# STM32F103C8T6.net
KiCad netlist of a schematic drawn in Altium Designer
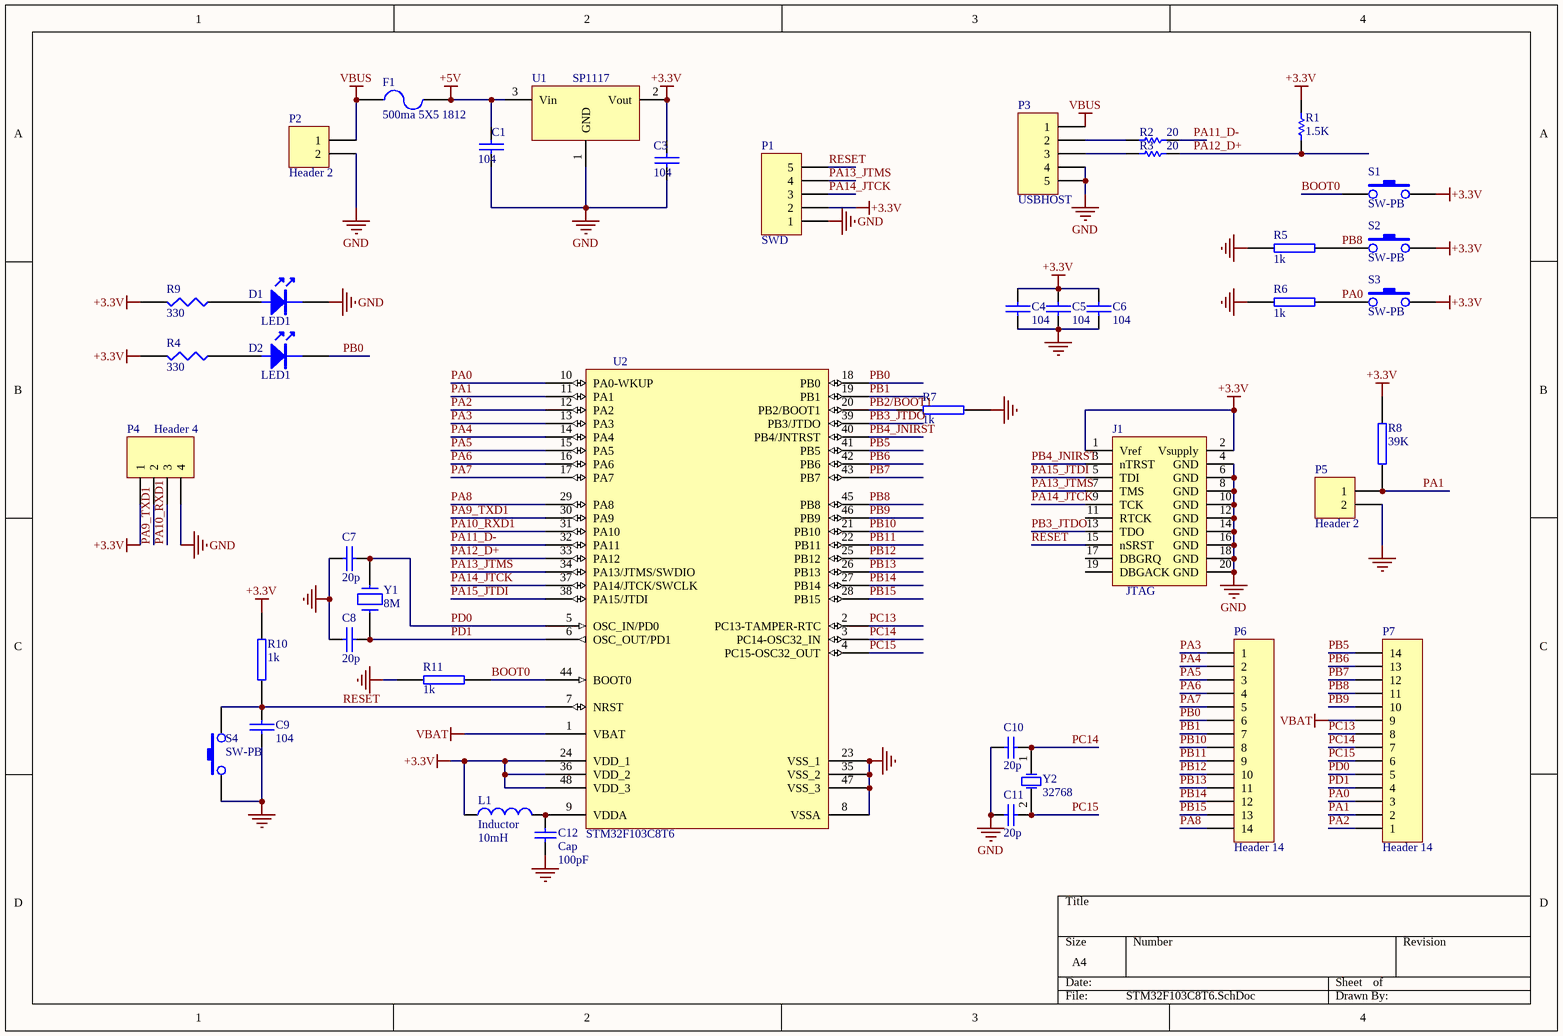
[diagram p0: STM32F103C8T6.SchDoc]

(export (version "E")
  (design (tool "Eeschema 10.0.6"))
  (components
    (comp (ref "C1")
      (value "104")
      (footprint "0805C1")
      (description "Capacitor")
      (libsource (lib "*") (part "CAP"))
    )
    (comp (ref "C3")
      (value "104")
      (footprint "0805C1")
      (description "Capacitor")
      (libsource (lib "*") (part "CAP"))
    )
    (comp (ref "C4")
      (value "104")
      (footprint "0805C1")
      (description "Capacitor")
      (libsource (lib "*") (part "CAP"))
    )
    (comp (ref "C5")
      (value "104")
      (footprint "0805C1")
      (description "Capacitor")
      (libsource (lib "*") (part "CAP"))
    )
    (comp (ref "C6")
      (value "104")
      (footprint "0805C1")
      (description "Capacitor")
      (libsource (lib "*") (part "CAP"))
    )
    (comp (ref "C7")
      (value "20p")
      (footprint "0805C1")
      (description "Capacitor")
      (libsource (lib "*") (part "CAP"))
    )
    (comp (ref "C8")
      (value "20p")
      (footprint "0805C1")
      (description "Capacitor")
      (libsource (lib "*") (part "CAP"))
    )
    (comp (ref "C9")
      (value "104")
      (footprint "0805C1")
      (description "Capacitor")
      (libsource (lib "*") (part "CAP"))
    )
    (comp (ref "C10")
      (value "20p")
      (footprint "0805C1")
      (description "Capacitor")
      (fields (field (name "Comment") "Cap") (field (name "PUBLISHER") "Altium Limited"))
      (libsource (lib "Miscellaneous Devices") (part "Cap"))
    )
    (comp (ref "C11")
      (value "20p")
      (footprint "0805C1")
      (description "Capacitor")
      (fields (field (name "Comment") "Cap") (field (name "PUBLISHER") "Altium Limited"))
      (libsource (lib "Miscellaneous Devices") (part "Cap"))
    )
    (comp (ref "C12")
      (value "Cap")
      (footprint "0805C1")
      (description "Capacitor")
      (fields (field (name "ALTIUM_VALUE") "100pF") (field (name "PUBLISHER") "Altium Limited"))
      (libsource (lib "Miscellaneous Devices") (part "Cap"))
    )
    (comp (ref "D1") (value "LED1") (footprint "0805LED") (libsource (lib "*") (part "LED")))
    (comp (ref "D2") (value "LED1") (footprint "0805LED") (libsource (lib "*") (part "LED")))
    (comp (ref "F1")
      (value "500ma 5X5 1812")
      (footprint "1812R")
      (description "Fuse")
      (fields (field (name "PUBLISHER") "Altium Limited"))
      (libsource (lib "Miscellaneous Devices") (part "Fuse 2"))
    )
    (comp (ref "J1") (value "JTAG") (footprint "HDR2X10") (libsource (lib "hhic") (part "JTAG")))
    (comp (ref "L1")
      (value "Inductor")
      (footprint "0805R1")
      (fields (field (name "ALTIUM_VALUE") "10mH") (field (name "PUBLISHER") "Altium Limited"))
      (libsource (lib "Miscellaneous Devices") (part "Inductor"))
    )
    (comp (ref "P1")
      (value "SWD")
      (footprint "HDR1X5")
      (description "Header, 5-Pin")
      (fields (field (name "PUBLISHER") "Altium Limited"))
      (libsource (lib "") (part "Header 5_1"))
    )
    (comp (ref "P2")
      (value "Header 2")
      (footprint "5VINPUT")
      (description "Header, 2-Pin")
      (fields (field (name "PUBLISHER") "Altium Limited"))
      (libsource (lib "Miscellaneous Connectors") (part "Header 2"))
    )
    (comp (ref "P3")
      (value "USBHOST")
      (footprint "USB_mini")
      (description "Header, 5-Pin")
      (fields (field (name "PUBLISHER") "Altium Limited"))
      (libsource (lib "Miscellaneous Connectors") (part "Header 5"))
    )
    (comp (ref "P4")
      (value "Header 4")
      (footprint "HDR1X4")
      (description "Header, 4-Pin")
      (fields (field (name "PUBLISHER") "Altium Limited"))
      (libsource (lib "Miscellaneous Connectors") (part "Header 4"))
    )
    (comp (ref "P5")
      (value "Header 2")
      (footprint "HDR1X2")
      (description "Header, 2-Pin")
      (fields (field (name "PUBLISHER") "Altium Limited"))
      (libsource (lib "Miscellaneous Connectors") (part "Header 2"))
    )
    (comp (ref "P6")
      (value "Header 14")
      (footprint "HDR1X14")
      (description "Header, 14-Pin")
      (fields (field (name "PUBLISHER") "Altium Limited"))
      (libsource (lib "Miscellaneous Connectors") (part "Header 14"))
    )
    (comp (ref "P7")
      (value "Header 14")
      (footprint "HDR1X14")
      (description "Header, 14-Pin")
      (fields (field (name "PUBLISHER") "Altium Limited"))
      (libsource (lib "") (part "Header 14_1"))
    )
    (comp (ref "R1")
      (value "1.5K")
      (footprint "0805R1")
      (description "Semiconductor Resistor")
      (fields (field (name "Comment") "Res Semi") (field (name "PUBLISHER") "Altium Limited"))
      (libsource (lib "Miscellaneous Devices") (part "Res Semi"))
    )
    (comp (ref "R2")
      (value "20")
      (footprint "0805R1")
      (description "Semiconductor Resistor")
      (fields (field (name "Comment") "Res Semi") (field (name "PUBLISHER") "Altium Limited"))
      (libsource (lib "Miscellaneous Devices") (part "Res Semi"))
    )
    (comp (ref "R3")
      (value "20")
      (footprint "0805R1")
      (description "Semiconductor Resistor")
      (fields (field (name "Comment") "Res Semi") (field (name "PUBLISHER") "Altium Limited"))
      (libsource (lib "Miscellaneous Devices") (part "Res Semi"))
    )
    (comp (ref "R4") (value "330") (footprint "0805R1") (libsource (lib "*") (part "RES1")))
    (comp (ref "R5") (value "1k") (footprint "0805R1") (libsource (lib "*") (part "RES2")))
    (comp (ref "R6") (value "1k") (footprint "0805R1") (libsource (lib "*") (part "RES2")))
    (comp (ref "R7") (value "1k") (footprint "0805R1") (libsource (lib "*") (part "RES2")))
    (comp (ref "R8") (value "39K") (footprint "0805R1") (libsource (lib "*") (part "RES2")))
    (comp (ref "R9") (value "330") (footprint "0805R1") (libsource (lib "*") (part "RES1")))
    (comp (ref "R10") (value "1k") (footprint "0805R1") (libsource (lib "*") (part "RES2")))
    (comp (ref "R11") (value "1k") (footprint "0805R1") (libsource (lib "*") (part "RES2")))
    (comp (ref "S1") (value "SW-PB") (footprint "KEY_5*5*X") (libsource (lib "*") (part "SW-PB")))
    (comp (ref "S2") (value "SW-PB") (footprint "KEY_5*5*X") (libsource (lib "*") (part "SW-PB")))
    (comp (ref "S3") (value "SW-PB") (footprint "KEY_5*5*X") (libsource (lib "*") (part "SW-PB")))
    (comp (ref "S4") (value "SW-PB") (footprint "KEY_5*5*X") (libsource (lib "*") (part "SW-PB")))
    (comp (ref "U1") (value "SP1117") (footprint "SOT-223") (libsource (lib "hhregulator") (part "SP1117")))
    (comp (ref "U2")
      (value "STM32F103C8T6")
      (footprint "LQFP48_M")
      (description "STM32 ARM-based 32-bit MCU with 64 Kbytes Flash, 48-pin LQFP, Industrial Temperature")
      (fields (field (name "PUBLISHER") "*"))
      (libsource (lib "*") (part "STM32F103C8T6"))
    )
    (comp (ref "Y1")
      (value "8M")
      (footprint "XTAL_smd1")
      (description "Crystal")
      (libsource (lib "*") (part "CRYSTAL"))
    )
    (comp (ref "Y2")
      (value "32768")
      (footprint "XTAL_32768_HH")
      (description "Crystal Oscillator")
      (fields (field (name "PUBLISHER") "Altium Limited"))
      (libsource (lib "Miscellaneous Devices") (part "XTAL"))
    )
  )
  (nets
    (net (code "1") (name "+3.3V") (class "Default")
      (node (ref "C3") (pin "1") (pinfunction "1_1") (pintype "passive"))
      (node (ref "C4") (pin "2") (pinfunction "2_2") (pintype "passive"))
      (node (ref "C5") (pin "2") (pinfunction "2_2") (pintype "passive"))
      (node (ref "C6") (pin "2") (pinfunction "2_2") (pintype "passive"))
      (node (ref "J1") (pin "1") (pinfunction "Vref_1") (pintype "passive"))
      (node (ref "J1") (pin "2") (pinfunction "Vsupply_2") (pintype "passive"))
      (node (ref "L1") (pin "1") (pinfunction "1_1") (pintype "passive"))
      (node (ref "P1") (pin "2") (pinfunction "2_2") (pintype "passive"))
      (node (ref "P4") (pin "1") (pinfunction "1_1") (pintype "passive"))
      (node (ref "R1") (pin "1") (pinfunction "1_1") (pintype "passive"))
      (node (ref "R10") (pin "2") (pinfunction "2_2") (pintype "passive"))
      (node (ref "R4") (pin "2") (pinfunction "2_2") (pintype "passive"))
      (node (ref "R8") (pin "1") (pinfunction "1_1") (pintype "passive"))
      (node (ref "R9") (pin "2") (pinfunction "2_2") (pintype "passive"))
      (node (ref "S1") (pin "2") (pinfunction "2_2") (pintype "passive"))
      (node (ref "S2") (pin "1") (pinfunction "1_1") (pintype "passive"))
      (node (ref "S3") (pin "1") (pinfunction "1_1") (pintype "passive"))
      (node (ref "U1") (pin "2") (pinfunction "Vout_2") (pintype "passive"))
      (node (ref "U2") (pin "24") (pinfunction "VDD_1_24") (pintype "power_in"))
      (node (ref "U2") (pin "36") (pinfunction "VDD_2_36") (pintype "power_in"))
      (node (ref "U2") (pin "48") (pinfunction "VDD_3_48") (pintype "power_in"))
    )
    (net (code "2") (name "+5V") (class "Default")
      (node (ref "C1") (pin "1") (pinfunction "1_1") (pintype "passive"))
      (node (ref "F1") (pin "2") (pinfunction "2_2") (pintype "passive"))
      (node (ref "U1") (pin "3") (pinfunction "Vin_3") (pintype "passive"))
    )
    (net (code "3") (name "/BOOT0") (class "Default")
      (node (ref "R11") (pin "1") (pinfunction "1_1") (pintype "passive"))
      (node (ref "S1") (pin "1") (pinfunction "1_1") (pintype "passive"))
      (node (ref "U2") (pin "44") (pinfunction "BOOT0_44") (pintype "input"))
    )
    (net (code "4") (name "/PA0") (class "Default")
      (node (ref "P7") (pin "3") (pinfunction "3_3") (pintype "passive"))
      (node (ref "R6") (pin "1") (pinfunction "1_1") (pintype "passive"))
      (node (ref "S3") (pin "2") (pinfunction "2_2") (pintype "passive"))
      (node (ref "U2") (pin "10") (pinfunction "PA0-WKUP_10") (pintype "bidirectional"))
    )
    (net (code "5") (name "/PA1") (class "Default")
      (node (ref "P5") (pin "1") (pinfunction "1_1") (pintype "passive"))
      (node (ref "P7") (pin "2") (pinfunction "2_2") (pintype "passive"))
      (node (ref "R8") (pin "2") (pinfunction "2_2") (pintype "passive"))
      (node (ref "U2") (pin "11") (pinfunction "PA1_11") (pintype "bidirectional"))
    )
    (net (code "6") (name "/PA2") (class "Default")
      (node (ref "P7") (pin "1") (pinfunction "1_1") (pintype "passive"))
      (node (ref "U2") (pin "12") (pinfunction "PA2_12") (pintype "bidirectional"))
    )
    (net (code "7") (name "/PA3") (class "Default")
      (node (ref "P6") (pin "1") (pinfunction "1_1") (pintype "passive"))
      (node (ref "U2") (pin "13") (pinfunction "PA3_13") (pintype "bidirectional"))
    )
    (net (code "8") (name "/PA4") (class "Default")
      (node (ref "P6") (pin "2") (pinfunction "2_2") (pintype "passive"))
      (node (ref "U2") (pin "14") (pinfunction "PA4_14") (pintype "bidirectional"))
    )
    (net (code "9") (name "/PA5") (class "Default")
      (node (ref "P6") (pin "3") (pinfunction "3_3") (pintype "passive"))
      (node (ref "U2") (pin "15") (pinfunction "PA5_15") (pintype "bidirectional"))
    )
    (net (code "10") (name "/PA6") (class "Default")
      (node (ref "P6") (pin "4") (pinfunction "4_4") (pintype "passive"))
      (node (ref "U2") (pin "16") (pinfunction "PA6_16") (pintype "bidirectional"))
    )
    (net (code "11") (name "/PA7") (class "Default")
      (node (ref "P6") (pin "5") (pinfunction "5_5") (pintype "passive"))
      (node (ref "U2") (pin "17") (pinfunction "PA7_17") (pintype "bidirectional"))
    )
    (net (code "12") (name "/PA8") (class "Default")
      (node (ref "P6") (pin "14") (pinfunction "14_14") (pintype "passive"))
      (node (ref "U2") (pin "29") (pinfunction "PA8_29") (pintype "bidirectional"))
    )
    (net (code "13") (name "/PA9_TXD1") (class "Default")
      (node (ref "P4") (pin "2") (pinfunction "2_2") (pintype "passive"))
      (node (ref "U2") (pin "30") (pinfunction "PA9_30") (pintype "bidirectional"))
    )
    (net (code "14") (name "/PA10_RXD1") (class "Default")
      (node (ref "P4") (pin "3") (pinfunction "3_3") (pintype "passive"))
      (node (ref "U2") (pin "31") (pinfunction "PA10_31") (pintype "bidirectional"))
    )
    (net (code "15") (name "/PA11_D-") (class "Default")
      (node (ref "R2") (pin "2") (pinfunction "2_2") (pintype "passive"))
      (node (ref "U2") (pin "32") (pinfunction "PA11_32") (pintype "bidirectional"))
    )
    (net (code "16") (name "/PA12_D+") (class "Default")
      (node (ref "R1") (pin "2") (pinfunction "2_2") (pintype "passive"))
      (node (ref "R3") (pin "2") (pinfunction "2_2") (pintype "passive"))
      (node (ref "U2") (pin "33") (pinfunction "PA12_33") (pintype "bidirectional"))
    )
    (net (code "17") (name "/PA13_JTMS") (class "Default")
      (node (ref "J1") (pin "7") (pinfunction "TMS_7") (pintype "passive"))
      (node (ref "P1") (pin "4") (pinfunction "4_4") (pintype "passive"))
      (node (ref "U2") (pin "34") (pinfunction "PA13/JTMS/SWDIO_34") (pintype "bidirectional"))
    )
    (net (code "18") (name "/PA14_JTCK") (class "Default")
      (node (ref "J1") (pin "9") (pinfunction "TCK_9") (pintype "passive"))
      (node (ref "P1") (pin "3") (pinfunction "3_3") (pintype "passive"))
      (node (ref "U2") (pin "37") (pinfunction "PA14/JTCK/SWCLK_37") (pintype "bidirectional"))
    )
    (net (code "19") (name "/PA15_JTDI") (class "Default")
      (node (ref "J1") (pin "5") (pinfunction "TDI_5") (pintype "passive"))
      (node (ref "U2") (pin "38") (pinfunction "PA15/JTDI_38") (pintype "bidirectional"))
    )
    (net (code "20") (name "/PB0") (class "Default")
      (node (ref "D2") (pin "2") (pinfunction "2_2") (pintype "passive"))
      (node (ref "P6") (pin "6") (pinfunction "6_6") (pintype "passive"))
      (node (ref "U2") (pin "18") (pinfunction "PB0_18") (pintype "bidirectional"))
    )
    (net (code "21") (name "/PB1") (class "Default")
      (node (ref "P6") (pin "7") (pinfunction "7_7") (pintype "passive"))
      (node (ref "U2") (pin "19") (pinfunction "PB1_19") (pintype "bidirectional"))
    )
    (net (code "22") (name "/PB2{slash}BOOT1") (class "Default")
      (node (ref "R7") (pin "1") (pinfunction "1_1") (pintype "passive"))
      (node (ref "U2") (pin "20") (pinfunction "PB2/BOOT1_20") (pintype "bidirectional"))
    )
    (net (code "23") (name "/PB3_JTDO") (class "Default")
      (node (ref "J1") (pin "13") (pinfunction "TDO_13") (pintype "passive"))
      (node (ref "U2") (pin "39") (pinfunction "PB3/JTDO_39") (pintype "bidirectional"))
    )
    (net (code "24") (name "/PB4_JNIRST") (class "Default")
      (node (ref "J1") (pin "3") (pinfunction "nTRST_3") (pintype "passive"))
      (node (ref "U2") (pin "40") (pinfunction "PB4/JNTRST_40") (pintype "bidirectional"))
    )
    (net (code "25") (name "/PB5") (class "Default")
      (node (ref "P7") (pin "14") (pinfunction "14_14") (pintype "passive"))
      (node (ref "U2") (pin "41") (pinfunction "PB5_41") (pintype "bidirectional"))
    )
    (net (code "26") (name "/PB6") (class "Default")
      (node (ref "P7") (pin "13") (pinfunction "13_13") (pintype "passive"))
      (node (ref "U2") (pin "42") (pinfunction "PB6_42") (pintype "bidirectional"))
    )
    (net (code "27") (name "/PB7") (class "Default")
      (node (ref "P7") (pin "12") (pinfunction "12_12") (pintype "passive"))
      (node (ref "U2") (pin "43") (pinfunction "PB7_43") (pintype "bidirectional"))
    )
    (net (code "28") (name "/PB8") (class "Default")
      (node (ref "P7") (pin "11") (pinfunction "11_11") (pintype "passive"))
      (node (ref "R5") (pin "1") (pinfunction "1_1") (pintype "passive"))
      (node (ref "S2") (pin "2") (pinfunction "2_2") (pintype "passive"))
      (node (ref "U2") (pin "45") (pinfunction "PB8_45") (pintype "bidirectional"))
    )
    (net (code "29") (name "/PB9") (class "Default")
      (node (ref "P7") (pin "10") (pinfunction "10_10") (pintype "passive"))
      (node (ref "U2") (pin "46") (pinfunction "PB9_46") (pintype "bidirectional"))
    )
    (net (code "30") (name "/PB10") (class "Default")
      (node (ref "P6") (pin "8") (pinfunction "8_8") (pintype "passive"))
      (node (ref "U2") (pin "21") (pinfunction "PB10_21") (pintype "bidirectional"))
    )
    (net (code "31") (name "/PB11") (class "Default")
      (node (ref "P6") (pin "9") (pinfunction "9_9") (pintype "passive"))
      (node (ref "U2") (pin "22") (pinfunction "PB11_22") (pintype "bidirectional"))
    )
    (net (code "32") (name "/PB12") (class "Default")
      (node (ref "P6") (pin "10") (pinfunction "10_10") (pintype "passive"))
      (node (ref "U2") (pin "25") (pinfunction "PB12_25") (pintype "bidirectional"))
    )
    (net (code "33") (name "/PB13") (class "Default")
      (node (ref "P6") (pin "11") (pinfunction "11_11") (pintype "passive"))
      (node (ref "U2") (pin "26") (pinfunction "PB13_26") (pintype "bidirectional"))
    )
    (net (code "34") (name "/PB14") (class "Default")
      (node (ref "P6") (pin "12") (pinfunction "12_12") (pintype "passive"))
      (node (ref "U2") (pin "27") (pinfunction "PB14_27") (pintype "bidirectional"))
    )
    (net (code "35") (name "/PB15") (class "Default")
      (node (ref "P6") (pin "13") (pinfunction "13_13") (pintype "passive"))
      (node (ref "U2") (pin "28") (pinfunction "PB15_28") (pintype "bidirectional"))
    )
    (net (code "36") (name "/PC13") (class "Default")
      (node (ref "P7") (pin "8") (pinfunction "8_8") (pintype "passive"))
      (node (ref "U2") (pin "2") (pinfunction "PC13-TAMPER-RTC_2") (pintype "bidirectional"))
    )
    (net (code "37") (name "/PC14") (class "Default")
      (node (ref "C10") (pin "1") (pinfunction "1_1") (pintype "passive"))
      (node (ref "P7") (pin "7") (pinfunction "7_7") (pintype "passive"))
      (node (ref "U2") (pin "3") (pinfunction "PC14-OSC32_IN_3") (pintype "bidirectional"))
      (node (ref "Y2") (pin "1") (pinfunction "OSC1_1") (pintype "passive"))
    )
    (net (code "38") (name "/PC15") (class "Default")
      (node (ref "C11") (pin "1") (pinfunction "1_1") (pintype "passive"))
      (node (ref "P7") (pin "6") (pinfunction "6_6") (pintype "passive"))
      (node (ref "U2") (pin "4") (pinfunction "PC15-OSC32_OUT_4") (pintype "bidirectional"))
      (node (ref "Y2") (pin "2") (pinfunction "OSC2_2") (pintype "passive"))
    )
    (net (code "39") (name "/PD0") (class "Default")
      (node (ref "C7") (pin "2") (pinfunction "2_2") (pintype "passive"))
      (node (ref "P7") (pin "5") (pinfunction "5_5") (pintype "passive"))
      (node (ref "U2") (pin "5") (pinfunction "OSC_IN/PD0_5") (pintype "input"))
      (node (ref "Y1") (pin "1") (pinfunction "1_1") (pintype "passive"))
    )
    (net (code "40") (name "/PD1") (class "Default")
      (node (ref "C8") (pin "2") (pinfunction "2_2") (pintype "passive"))
      (node (ref "P7") (pin "4") (pinfunction "4_4") (pintype "passive"))
      (node (ref "U2") (pin "6") (pinfunction "OSC_OUT/PD1_6") (pintype "output"))
      (node (ref "Y1") (pin "2") (pinfunction "2_2") (pintype "passive"))
    )
    (net (code "41") (name "/RESET") (class "Default")
      (node (ref "C9") (pin "2") (pinfunction "2_2") (pintype "passive"))
      (node (ref "J1") (pin "15") (pinfunction "nSRST_15") (pintype "passive"))
      (node (ref "P1") (pin "5") (pinfunction "5_5") (pintype "passive"))
      (node (ref "R10") (pin "1") (pinfunction "1_1") (pintype "passive"))
      (node (ref "S4") (pin "2") (pinfunction "2_2") (pintype "passive"))
      (node (ref "U2") (pin "7") (pinfunction "NRST_7") (pintype "bidirectional"))
    )
    (net (code "42") (name "GND") (class "Default")
      (node (ref "C1") (pin "2") (pinfunction "2_2") (pintype "passive"))
      (node (ref "C10") (pin "2") (pinfunction "2_2") (pintype "passive"))
      (node (ref "C11") (pin "2") (pinfunction "2_2") (pintype "passive"))
      (node (ref "C12") (pin "1") (pinfunction "1_1") (pintype "passive"))
      (node (ref "C3") (pin "2") (pinfunction "2_2") (pintype "passive"))
      (node (ref "C4") (pin "1") (pinfunction "1_1") (pintype "passive"))
      (node (ref "C5") (pin "1") (pinfunction "1_1") (pintype "passive"))
      (node (ref "C6") (pin "1") (pinfunction "1_1") (pintype "passive"))
      (node (ref "C7") (pin "1") (pinfunction "1_1") (pintype "passive"))
      (node (ref "C8") (pin "1") (pinfunction "1_1") (pintype "passive"))
      (node (ref "C9") (pin "1") (pinfunction "1_1") (pintype "passive"))
      (node (ref "D1") (pin "2") (pinfunction "2_2") (pintype "passive"))
      (node (ref "J1") (pin "10") (pinfunction "GND_10") (pintype "passive"))
      (node (ref "J1") (pin "12") (pinfunction "GND_12") (pintype "passive"))
      (node (ref "J1") (pin "14") (pinfunction "GND_14") (pintype "passive"))
      (node (ref "J1") (pin "16") (pinfunction "GND_16") (pintype "passive"))
      (node (ref "J1") (pin "18") (pinfunction "GND_18") (pintype "passive"))
      (node (ref "J1") (pin "20") (pinfunction "GND_20") (pintype "passive"))
      (node (ref "J1") (pin "4") (pinfunction "GND_4") (pintype "passive"))
      (node (ref "J1") (pin "6") (pinfunction "GND_6") (pintype "passive"))
      (node (ref "J1") (pin "8") (pinfunction "GND_8") (pintype "passive"))
      (node (ref "P1") (pin "1") (pinfunction "1_1") (pintype "passive"))
      (node (ref "P2") (pin "2") (pinfunction "2_2") (pintype "passive"))
      (node (ref "P3") (pin "4") (pinfunction "4_4") (pintype "passive"))
      (node (ref "P3") (pin "5") (pinfunction "5_5") (pintype "passive"))
      (node (ref "P4") (pin "4") (pinfunction "4_4") (pintype "passive"))
      (node (ref "P5") (pin "2") (pinfunction "2_2") (pintype "passive"))
      (node (ref "R11") (pin "2") (pinfunction "2_2") (pintype "passive"))
      (node (ref "R5") (pin "2") (pinfunction "2_2") (pintype "passive"))
      (node (ref "R6") (pin "2") (pinfunction "2_2") (pintype "passive"))
      (node (ref "R7") (pin "2") (pinfunction "2_2") (pintype "passive"))
      (node (ref "S4") (pin "1") (pinfunction "1_1") (pintype "passive"))
      (node (ref "U1") (pin "1") (pinfunction "GND_1") (pintype "passive"))
      (node (ref "U2") (pin "23") (pinfunction "VSS_1_23") (pintype "power_in"))
      (node (ref "U2") (pin "35") (pinfunction "VSS_2_35") (pintype "power_in"))
      (node (ref "U2") (pin "47") (pinfunction "VSS_3_47") (pintype "power_in"))
      (node (ref "U2") (pin "8") (pinfunction "VSSA_8") (pintype "power_in"))
    )
    (net (code "43") (name "Net-(D1-Pad1)") (class "Default")
      (node (ref "D1") (pin "1") (pinfunction "1_1") (pintype "passive"))
      (node (ref "R9") (pin "1") (pinfunction "1_1") (pintype "passive"))
    )
    (net (code "44") (name "Net-(D2-Pad1)") (class "Default")
      (node (ref "D2") (pin "1") (pinfunction "1_1") (pintype "passive"))
      (node (ref "R4") (pin "1") (pinfunction "1_1") (pintype "passive"))
    )
    (net (code "45") (name "Net-(P3-Pad2)") (class "Default")
      (node (ref "P3") (pin "2") (pinfunction "2_2") (pintype "passive"))
      (node (ref "R2") (pin "1") (pinfunction "1_1") (pintype "passive"))
    )
    (net (code "46") (name "Net-(P3-Pad3)") (class "Default")
      (node (ref "P3") (pin "3") (pinfunction "3_3") (pintype "passive"))
      (node (ref "R3") (pin "1") (pinfunction "1_1") (pintype "passive"))
    )
    (net (code "47") (name "Net-(U2-VDDA)") (class "Default")
      (node (ref "C12") (pin "2") (pinfunction "2_2") (pintype "passive"))
      (node (ref "L1") (pin "2") (pinfunction "2_2") (pintype "passive"))
      (node (ref "U2") (pin "9") (pinfunction "VDDA_9") (pintype "power_in"))
    )
    (net (code "48") (name "VBAT") (class "Default")
      (node (ref "P7") (pin "9") (pinfunction "9_9") (pintype "passive"))
      (node (ref "U2") (pin "1") (pinfunction "VBAT_1") (pintype "power_in"))
    )
    (net (code "49") (name "VBUS") (class "Default")
      (node (ref "F1") (pin "1") (pinfunction "1_1") (pintype "passive"))
      (node (ref "P2") (pin "1") (pinfunction "1_1") (pintype "passive"))
      (node (ref "P3") (pin "1") (pinfunction "1_1") (pintype "passive"))
    )
    (net (code "50") (name "unconnected-(J1-DBGACK-Pad19)") (class "Default")
      (node (ref "J1") (pin "19") (pinfunction "DBGACK_19") (pintype "passive"))
    )
    (net (code "51") (name "unconnected-(J1-DBGRQ-Pad17)") (class "Default")
      (node (ref "J1") (pin "17") (pinfunction "DBGRQ_17") (pintype "passive"))
    )
    (net (code "52") (name "unconnected-(J1-RTCK-Pad11)") (class "Default")
      (node (ref "J1") (pin "11") (pinfunction "RTCK_11") (pintype "passive"))
    )
  )
)
